# VARIABLE_DC_SUPPLY_schematic.net
KiCad netlist of a schematic drawn in EAGLE
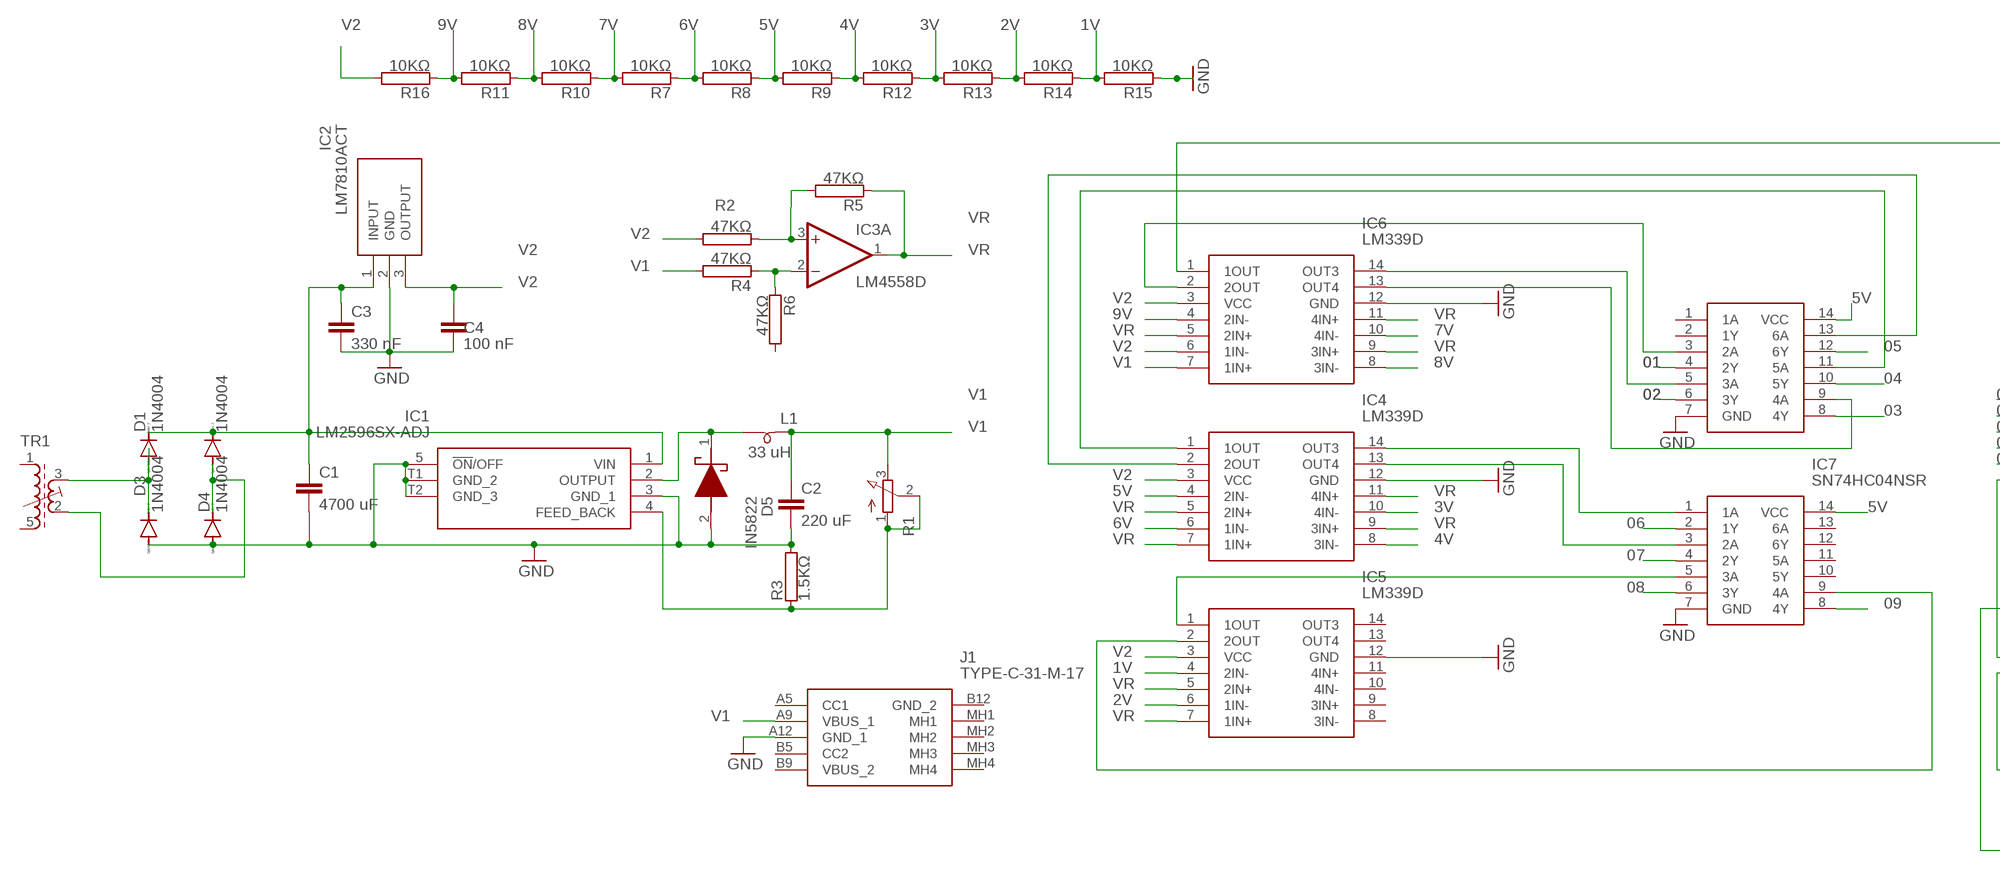
[diagram p0: schematic, sheet 1, part 1 of 2]
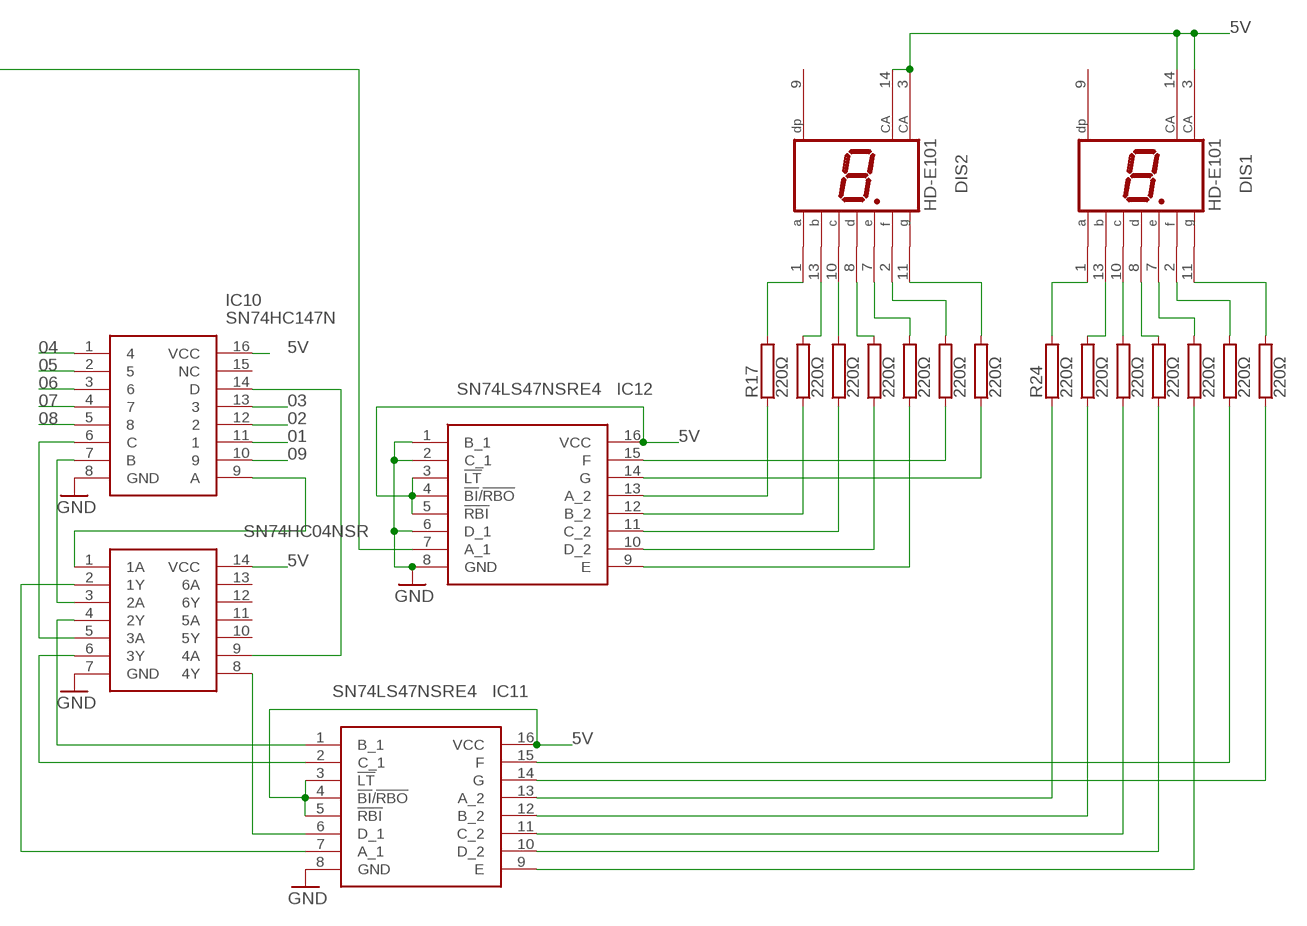
[diagram p1: schematic, sheet 1, part 2 of 2]

(export (version "E")
  (design (tool "Eeschema 10.0.6"))
  (components
    (comp (ref "C1")
      (value "4700 uF")
      (footprint "eagle-import:C2.5-2")
      (libsource (lib "eagle-import") (part "C2.5/2"))
    )
    (comp (ref "C2")
      (value "220 uF")
      (footprint "eagle-import:C2.5-2")
      (libsource (lib "eagle-import") (part "C2.5/2"))
    )
    (comp (ref "C3")
      (value "330 nF")
      (footprint "eagle-import:C2.5-2")
      (libsource (lib "eagle-import") (part "C2.5/2"))
    )
    (comp (ref "C4")
      (value "100 nF")
      (footprint "eagle-import:C2.5-2")
      (libsource (lib "eagle-import") (part "C2.5/2"))
    )
    (comp (ref "D1")
      (value "1N4004")
      (footprint "eagle-import:DO41-10")
      (libsource (lib "eagle-import") (part "1N4004"))
    )
    (comp (ref "D2")
      (value "1N4004")
      (footprint "eagle-import:DO41-10")
      (libsource (lib "eagle-import") (part "1N4004"))
    )
    (comp (ref "D3")
      (value "1N4004")
      (footprint "eagle-import:DO41-10")
      (libsource (lib "eagle-import") (part "1N4004"))
    )
    (comp (ref "D4")
      (value "1N4004")
      (footprint "eagle-import:DO41-10")
      (libsource (lib "eagle-import") (part "1N4004"))
    )
    (comp (ref "D5")
      (value "IN5822")
      (footprint "eagle-import:DIOAD3020W130L900D530")
      (libsource (lib "eagle-import") (part "IN5822"))
    )
    (comp (ref "DIS1")
      (value "HD-E101")
      (footprint "eagle-import:HDSP-I")
      (libsource (lib "eagle-import") (part "HD-E101"))
    )
    (comp (ref "DIS2")
      (value "HD-E101")
      (footprint "eagle-import:HDSP-I")
      (libsource (lib "eagle-import") (part "HD-E101"))
    )
    (comp (ref "IC1")
      (value "LM2596SX-ADJ")
      (footprint "eagle-import:LM2596SXADJ")
      (fields (field (name "MOUSER_PART_NUMBER") "926-LM2596SX-ADJ"))
      (libsource (lib "eagle-import") (part "LM2596SX-ADJ"))
    )
    (comp (ref "IC2")
      (value "LM7810ACT")
      (footprint "eagle-import:TO254P470X1016X2019-3P")
      (fields (field (name "MOUSER_PART_NUMBER") "512-LM7810ACT"))
      (libsource (lib "eagle-import") (part "LM7810ACT"))
    )
    (comp (ref "IC3")
      (value "LM4558D")
      (footprint "eagle-import:SO08")
      (libsource (lib "eagle-import") (part "4558DLM"))
    )
    (comp (ref "IC4")
      (value "LM339D")
      (footprint "eagle-import:SOIC127P600X175-14N")
      (fields (field (name "MOUSER_PART_NUMBER") "595-LM339D"))
      (libsource (lib "eagle-import") (part "LM339D"))
    )
    (comp (ref "IC5")
      (value "LM339D")
      (footprint "eagle-import:SOIC127P600X175-14N")
      (fields (field (name "MOUSER_PART_NUMBER") "595-LM339D"))
      (libsource (lib "eagle-import") (part "LM339D"))
    )
    (comp (ref "IC6")
      (value "LM339D")
      (footprint "eagle-import:SOIC127P600X175-14N")
      (fields (field (name "MOUSER_PART_NUMBER") "595-LM339D"))
      (libsource (lib "eagle-import") (part "LM339D"))
    )
    (comp (ref "IC7")
      (value "SN74HC04NSR")
      (footprint "eagle-import:SOIC127P780X200-14N")
      (fields (field (name "MOUSER_PART_NUMBER") "595-SN74HC04NSR"))
      (libsource (lib "eagle-import") (part "SN74HC04NSR"))
    )
    (comp (ref "IC8")
      (value "SN74HC04NSR")
      (footprint "eagle-import:SOIC127P780X200-14N")
      (fields (field (name "MOUSER_PART_NUMBER") "595-SN74HC04NSR"))
      (libsource (lib "eagle-import") (part "SN74HC04NSR"))
    )
    (comp (ref "IC9")
      (value "SN74HC04NSR")
      (footprint "eagle-import:SOIC127P780X200-14N")
      (fields (field (name "MOUSER_PART_NUMBER") "595-SN74HC04NSR"))
      (libsource (lib "eagle-import") (part "SN74HC04NSR"))
    )
    (comp (ref "IC10")
      (value "SN74HC147N")
      (footprint "eagle-import:DIP794W53P254L1930H508Q16N")
      (libsource (lib "eagle-import") (part "SN74HC147N"))
    )
    (comp (ref "IC11")
      (value "SN74LS47NSRE4")
      (footprint "eagle-import:SOIC127P780X200-16N")
      (libsource (lib "eagle-import") (part "SN74LS47NSRE4"))
    )
    (comp (ref "IC12")
      (value "SN74LS47NSRE4")
      (footprint "eagle-import:SOIC127P780X200-16N")
      (libsource (lib "eagle-import") (part "SN74LS47NSRE4"))
    )
    (comp (ref "J1")
      (value "TYPE-C-31-M-17")
      (footprint "eagle-import:TYPEC31M17")
      (libsource (lib "eagle-import") (part "TYPE-C-31-M-17"))
    )
    (comp (ref "L1")
      (value "33 uH")
      (footprint "eagle-import:SM-B5")
      (libsource (lib "eagle-import") (part "SM-B5"))
    )
    (comp (ref "R1")
      (value "3RP/1610N")
      (footprint "eagle-import:3RP_1610N")
      (libsource (lib "eagle-import") (part "3RP/1610N"))
    )
    (comp (ref "R2")
      (value "47KΩ")
      (footprint "eagle-import:TO-247-2V")
      (libsource (lib "eagle-import") (part "RMG100-V"))
    )
    (comp (ref "R3")
      (value "1.5KΩ")
      (footprint "eagle-import:TO-247-2V")
      (libsource (lib "eagle-import") (part "RMG100-V"))
    )
    (comp (ref "R4")
      (value "47KΩ")
      (footprint "eagle-import:TO-247-2V")
      (libsource (lib "eagle-import") (part "RMG100-V"))
    )
    (comp (ref "R5")
      (value "47KΩ")
      (footprint "eagle-import:TO-247-2V")
      (libsource (lib "eagle-import") (part "RMG100-V"))
    )
    (comp (ref "R6")
      (value "47KΩ")
      (footprint "eagle-import:TO-247-2V")
      (libsource (lib "eagle-import") (part "RMG100-V"))
    )
    (comp (ref "R7")
      (value "10KΩ")
      (footprint "eagle-import:TO-247-2V")
      (libsource (lib "eagle-import") (part "RMG100-V"))
    )
    (comp (ref "R8")
      (value "10KΩ")
      (footprint "eagle-import:TO-247-2V")
      (libsource (lib "eagle-import") (part "RMG100-V"))
    )
    (comp (ref "R9")
      (value "10KΩ")
      (footprint "eagle-import:TO-247-2V")
      (libsource (lib "eagle-import") (part "RMG100-V"))
    )
    (comp (ref "R10")
      (value "10KΩ")
      (footprint "eagle-import:TO-247-2V")
      (libsource (lib "eagle-import") (part "RMG100-V"))
    )
    (comp (ref "R11")
      (value "10KΩ")
      (footprint "eagle-import:TO-247-2V")
      (libsource (lib "eagle-import") (part "RMG100-V"))
    )
    (comp (ref "R12")
      (value "10KΩ")
      (footprint "eagle-import:TO-247-2V")
      (libsource (lib "eagle-import") (part "RMG100-V"))
    )
    (comp (ref "R13")
      (value "10KΩ")
      (footprint "eagle-import:TO-247-2V")
      (libsource (lib "eagle-import") (part "RMG100-V"))
    )
    (comp (ref "R14")
      (value "10KΩ")
      (footprint "eagle-import:TO-247-2V")
      (libsource (lib "eagle-import") (part "RMG100-V"))
    )
    (comp (ref "R15")
      (value "10KΩ")
      (footprint "eagle-import:TO-247-2V")
      (libsource (lib "eagle-import") (part "RMG100-V"))
    )
    (comp (ref "R16")
      (value "10KΩ")
      (footprint "eagle-import:TO-247-2V")
      (libsource (lib "eagle-import") (part "RMG100-V"))
    )
    (comp (ref "R17")
      (value "220Ω")
      (footprint "eagle-import:TO-247-2V")
      (libsource (lib "eagle-import") (part "RMG100-V"))
    )
    (comp (ref "R18")
      (value "220Ω")
      (footprint "eagle-import:TO-247-2V")
      (libsource (lib "eagle-import") (part "RMG100-V"))
    )
    (comp (ref "R19")
      (value "220Ω")
      (footprint "eagle-import:TO-247-2V")
      (libsource (lib "eagle-import") (part "RMG100-V"))
    )
    (comp (ref "R20")
      (value "220Ω")
      (footprint "eagle-import:TO-247-2V")
      (libsource (lib "eagle-import") (part "RMG100-V"))
    )
    (comp (ref "R21")
      (value "220Ω")
      (footprint "eagle-import:TO-247-2V")
      (libsource (lib "eagle-import") (part "RMG100-V"))
    )
    (comp (ref "R22")
      (value "220Ω")
      (footprint "eagle-import:TO-247-2V")
      (libsource (lib "eagle-import") (part "RMG100-V"))
    )
    (comp (ref "R23")
      (value "220Ω")
      (footprint "eagle-import:TO-247-2V")
      (libsource (lib "eagle-import") (part "RMG100-V"))
    )
    (comp (ref "R24")
      (value "220Ω")
      (footprint "eagle-import:TO-247-2V")
      (libsource (lib "eagle-import") (part "RMG100-V"))
    )
    (comp (ref "R25")
      (value "220Ω")
      (footprint "eagle-import:TO-247-2V")
      (libsource (lib "eagle-import") (part "RMG100-V"))
    )
    (comp (ref "R26")
      (value "220Ω")
      (footprint "eagle-import:TO-247-2V")
      (libsource (lib "eagle-import") (part "RMG100-V"))
    )
    (comp (ref "R27")
      (value "220Ω")
      (footprint "eagle-import:TO-247-2V")
      (libsource (lib "eagle-import") (part "RMG100-V"))
    )
    (comp (ref "R28")
      (value "220Ω")
      (footprint "eagle-import:TO-247-2V")
      (libsource (lib "eagle-import") (part "RMG100-V"))
    )
    (comp (ref "R29")
      (value "220Ω")
      (footprint "eagle-import:TO-247-2V")
      (libsource (lib "eagle-import") (part "RMG100-V"))
    )
    (comp (ref "R30")
      (value "220Ω")
      (footprint "eagle-import:TO-247-2V")
      (libsource (lib "eagle-import") (part "RMG100-V"))
    )
    (comp (ref "TR1")
      (value "71-4-1532")
      (footprint "eagle-import:71-5")
      (libsource (lib "eagle-import") (part "71-4-1532"))
    )
  )
  (nets
    (net (code "1") (name "/01") (class "Default")
      (node (ref "IC10") (pin "11") (pinfunction "1_11") (pintype "bidirectional"))
      (node (ref "IC8") (pin "4") (pinfunction "2Y_4") (pintype "bidirectional"))
    )
    (net (code "2") (name "/1V") (class "Default")
      (node (ref "IC5") (pin "4") (pinfunction "2IN-_4") (pintype "bidirectional"))
      (node (ref "R14") (pin "1") (pinfunction "1_1") (pintype "passive"))
      (node (ref "R15") (pin "2") (pinfunction "2_2") (pintype "passive"))
    )
    (net (code "3") (name "/02") (class "Default")
      (node (ref "IC10") (pin "12") (pinfunction "2_12") (pintype "bidirectional"))
      (node (ref "IC8") (pin "6") (pinfunction "3Y_6") (pintype "bidirectional"))
    )
    (net (code "4") (name "/2V") (class "Default")
      (node (ref "IC5") (pin "6") (pinfunction "1IN-_6") (pintype "bidirectional"))
      (node (ref "R13") (pin "1") (pinfunction "1_1") (pintype "passive"))
      (node (ref "R14") (pin "2") (pinfunction "2_2") (pintype "passive"))
    )
    (net (code "5") (name "/03") (class "Default")
      (node (ref "IC10") (pin "13") (pinfunction "3_13") (pintype "bidirectional"))
      (node (ref "IC8") (pin "8") (pinfunction "4Y_8") (pintype "bidirectional"))
    )
    (net (code "6") (name "/3V") (class "Default")
      (node (ref "IC4") (pin "10") (pinfunction "4IN-_10") (pintype "bidirectional"))
      (node (ref "R12") (pin "1") (pinfunction "1_1") (pintype "passive"))
      (node (ref "R13") (pin "2") (pinfunction "2_2") (pintype "passive"))
    )
    (net (code "7") (name "/04") (class "Default")
      (node (ref "IC10") (pin "1") (pinfunction "4_1") (pintype "bidirectional"))
      (node (ref "IC8") (pin "10") (pinfunction "5Y_10") (pintype "bidirectional"))
    )
    (net (code "8") (name "/4V") (class "Default")
      (node (ref "IC4") (pin "8") (pinfunction "3IN-_8") (pintype "bidirectional"))
      (node (ref "R12") (pin "2") (pinfunction "2_2") (pintype "passive"))
      (node (ref "R9") (pin "1") (pinfunction "1_1") (pintype "passive"))
    )
    (net (code "9") (name "/05") (class "Default")
      (node (ref "IC10") (pin "2") (pinfunction "5_2") (pintype "bidirectional"))
      (node (ref "IC8") (pin "12") (pinfunction "6Y_12") (pintype "bidirectional"))
    )
    (net (code "10") (name "/5V") (class "Default")
      (node (ref "DIS1") (pin "14") (pinfunction "CA_14") (pintype "passive"))
      (node (ref "DIS1") (pin "3") (pinfunction "CA_3") (pintype "passive"))
      (node (ref "DIS2") (pin "14") (pinfunction "CA_14") (pintype "passive"))
      (node (ref "DIS2") (pin "3") (pinfunction "CA_3") (pintype "passive"))
      (node (ref "IC10") (pin "16") (pinfunction "VCC_16") (pintype "bidirectional"))
      (node (ref "IC11") (pin "16") (pinfunction "VCC_16") (pintype "bidirectional"))
      (node (ref "IC11") (pin "3") (pinfunction "~{LT}_3") (pintype "bidirectional"))
      (node (ref "IC11") (pin "4") (pinfunction "~{BI}/~{RBO}_4") (pintype "bidirectional"))
      (node (ref "IC11") (pin "5") (pinfunction "~{RBI}_5") (pintype "bidirectional"))
      (node (ref "IC12") (pin "16") (pinfunction "VCC_16") (pintype "bidirectional"))
      (node (ref "IC12") (pin "3") (pinfunction "~{LT}_3") (pintype "bidirectional"))
      (node (ref "IC12") (pin "4") (pinfunction "~{BI}/~{RBO}_4") (pintype "bidirectional"))
      (node (ref "IC12") (pin "5") (pinfunction "~{RBI}_5") (pintype "bidirectional"))
      (node (ref "IC4") (pin "4") (pinfunction "2IN-_4") (pintype "bidirectional"))
      (node (ref "IC7") (pin "14") (pinfunction "VCC_14") (pintype "bidirectional"))
      (node (ref "IC8") (pin "14") (pinfunction "VCC_14") (pintype "bidirectional"))
      (node (ref "IC9") (pin "14") (pinfunction "VCC_14") (pintype "bidirectional"))
      (node (ref "R8") (pin "1") (pinfunction "1_1") (pintype "passive"))
      (node (ref "R9") (pin "2") (pinfunction "2_2") (pintype "passive"))
    )
    (net (code "11") (name "/06") (class "Default")
      (node (ref "IC10") (pin "3") (pinfunction "6_3") (pintype "bidirectional"))
      (node (ref "IC7") (pin "2") (pinfunction "1Y_2") (pintype "bidirectional"))
    )
    (net (code "12") (name "/6V") (class "Default")
      (node (ref "IC4") (pin "6") (pinfunction "1IN-_6") (pintype "bidirectional"))
      (node (ref "R7") (pin "1") (pinfunction "1_1") (pintype "passive"))
      (node (ref "R8") (pin "2") (pinfunction "2_2") (pintype "passive"))
    )
    (net (code "13") (name "/07") (class "Default")
      (node (ref "IC10") (pin "4") (pinfunction "7_4") (pintype "bidirectional"))
      (node (ref "IC7") (pin "4") (pinfunction "2Y_4") (pintype "bidirectional"))
    )
    (net (code "14") (name "/7V") (class "Default")
      (node (ref "IC6") (pin "10") (pinfunction "4IN-_10") (pintype "bidirectional"))
      (node (ref "R10") (pin "1") (pinfunction "1_1") (pintype "passive"))
      (node (ref "R7") (pin "2") (pinfunction "2_2") (pintype "passive"))
    )
    (net (code "15") (name "/08") (class "Default")
      (node (ref "IC10") (pin "5") (pinfunction "8_5") (pintype "bidirectional"))
      (node (ref "IC7") (pin "6") (pinfunction "3Y_6") (pintype "bidirectional"))
    )
    (net (code "16") (name "/8V") (class "Default")
      (node (ref "IC6") (pin "8") (pinfunction "3IN-_8") (pintype "bidirectional"))
      (node (ref "R10") (pin "2") (pinfunction "2_2") (pintype "passive"))
      (node (ref "R11") (pin "1") (pinfunction "1_1") (pintype "passive"))
    )
    (net (code "17") (name "/09") (class "Default")
      (node (ref "IC10") (pin "10") (pinfunction "9_10") (pintype "bidirectional"))
      (node (ref "IC7") (pin "8") (pinfunction "4Y_8") (pintype "bidirectional"))
    )
    (net (code "18") (name "/9V") (class "Default")
      (node (ref "IC6") (pin "4") (pinfunction "2IN-_4") (pintype "bidirectional"))
      (node (ref "R11") (pin "2") (pinfunction "2_2") (pintype "passive"))
      (node (ref "R16") (pin "1") (pinfunction "1_1") (pintype "passive"))
    )
    (net (code "19") (name "/V1") (class "Default")
      (node (ref "C2") (pin "1") (pinfunction "1_1") (pintype "passive"))
      (node (ref "IC6") (pin "7") (pinfunction "1IN+_7") (pintype "bidirectional"))
      (node (ref "J1") (pin "A9") (pinfunction "VBUS_1_A9") (pintype "bidirectional"))
      (node (ref "L1") (pin "2") (pinfunction "2_2") (pintype "passive"))
      (node (ref "R1") (pin "3") (pinfunction "E_3") (pintype "passive"))
      (node (ref "R4") (pin "2") (pinfunction "2_2") (pintype "passive"))
    )
    (net (code "20") (name "/V2") (class "Default")
      (node (ref "C4") (pin "1") (pinfunction "1_1") (pintype "passive"))
      (node (ref "IC2") (pin "3") (pinfunction "OUTPUT_3") (pintype "bidirectional"))
      (node (ref "IC4") (pin "3") (pinfunction "VCC_3") (pintype "bidirectional"))
      (node (ref "IC5") (pin "3") (pinfunction "VCC_3") (pintype "bidirectional"))
      (node (ref "IC6") (pin "3") (pinfunction "VCC_3") (pintype "bidirectional"))
      (node (ref "IC6") (pin "6") (pinfunction "1IN-_6") (pintype "bidirectional"))
      (node (ref "R16") (pin "2") (pinfunction "2_2") (pintype "passive"))
      (node (ref "R2") (pin "2") (pinfunction "2_2") (pintype "passive"))
    )
    (net (code "21") (name "/VR") (class "Default")
      (node (ref "IC3") (pin "1") (pinfunction "OUT_1") (pintype "output"))
      (node (ref "IC4") (pin "11") (pinfunction "4IN+_11") (pintype "bidirectional"))
      (node (ref "IC4") (pin "5") (pinfunction "2IN+_5") (pintype "bidirectional"))
      (node (ref "IC4") (pin "7") (pinfunction "1IN+_7") (pintype "bidirectional"))
      (node (ref "IC4") (pin "9") (pinfunction "3IN+_9") (pintype "bidirectional"))
      (node (ref "IC5") (pin "5") (pinfunction "2IN+_5") (pintype "bidirectional"))
      (node (ref "IC5") (pin "7") (pinfunction "1IN+_7") (pintype "bidirectional"))
      (node (ref "IC6") (pin "11") (pinfunction "4IN+_11") (pintype "bidirectional"))
      (node (ref "IC6") (pin "5") (pinfunction "2IN+_5") (pintype "bidirectional"))
      (node (ref "IC6") (pin "9") (pinfunction "3IN+_9") (pintype "bidirectional"))
      (node (ref "R5") (pin "1") (pinfunction "1_1") (pintype "passive"))
    )
    (net (code "22") (name "GND") (class "Default")
      (node (ref "C1") (pin "2") (pinfunction "2_2") (pintype "passive"))
      (node (ref "C2") (pin "2") (pinfunction "2_2") (pintype "passive"))
      (node (ref "C3") (pin "2") (pinfunction "2_2") (pintype "passive"))
      (node (ref "C4") (pin "2") (pinfunction "2_2") (pintype "passive"))
      (node (ref "D3") (pin "A") (pinfunction "A_A") (pintype "passive"))
      (node (ref "D4") (pin "A") (pinfunction "A_A") (pintype "passive"))
      (node (ref "D5") (pin "2") (pinfunction "A_2") (pintype "bidirectional"))
      (node (ref "IC1") (pin "3") (pinfunction "GND_1_3") (pintype "bidirectional"))
      (node (ref "IC1") (pin "5") (pinfunction "~{ON}/OFF_5") (pintype "bidirectional"))
      (node (ref "IC1") (pin "T1") (pinfunction "GND_2_T1") (pintype "bidirectional"))
      (node (ref "IC1") (pin "T2") (pinfunction "GND_3_T2") (pintype "bidirectional"))
      (node (ref "IC10") (pin "8") (pinfunction "GND_8") (pintype "bidirectional"))
      (node (ref "IC11") (pin "8") (pinfunction "GND_8") (pintype "bidirectional"))
      (node (ref "IC12") (pin "1") (pinfunction "B_1_1") (pintype "bidirectional"))
      (node (ref "IC12") (pin "2") (pinfunction "C_1_2") (pintype "bidirectional"))
      (node (ref "IC12") (pin "6") (pinfunction "D_1_6") (pintype "bidirectional"))
      (node (ref "IC12") (pin "8") (pinfunction "GND_8") (pintype "bidirectional"))
      (node (ref "IC2") (pin "2") (pinfunction "GND_2") (pintype "bidirectional"))
      (node (ref "IC4") (pin "12") (pinfunction "GND_12") (pintype "bidirectional"))
      (node (ref "IC5") (pin "12") (pinfunction "GND_12") (pintype "bidirectional"))
      (node (ref "IC6") (pin "12") (pinfunction "GND_12") (pintype "bidirectional"))
      (node (ref "IC7") (pin "7") (pinfunction "GND_7") (pintype "bidirectional"))
      (node (ref "IC8") (pin "7") (pinfunction "GND_7") (pintype "bidirectional"))
      (node (ref "IC9") (pin "7") (pinfunction "GND_7") (pintype "bidirectional"))
      (node (ref "J1") (pin "A12") (pinfunction "GND_1_A12") (pintype "bidirectional"))
      (node (ref "R15") (pin "1") (pinfunction "1_1") (pintype "passive"))
      (node (ref "R3") (pin "2") (pinfunction "2_2") (pintype "passive"))
    )
    (net (code "23") (name "Net-(D5-K)") (class "Default")
      (node (ref "D5") (pin "1") (pinfunction "K_1") (pintype "bidirectional"))
      (node (ref "IC1") (pin "2") (pinfunction "OUTPUT_2") (pintype "bidirectional"))
      (node (ref "L1") (pin "1") (pinfunction "1_1") (pintype "passive"))
    )
    (net (code "24") (name "Net-(DIS1-A)") (class "Default")
      (node (ref "DIS1") (pin "1") (pinfunction "A_1") (pintype "passive"))
      (node (ref "R24") (pin "2") (pinfunction "2_2") (pintype "passive"))
    )
    (net (code "25") (name "Net-(DIS1-B)") (class "Default")
      (node (ref "DIS1") (pin "13") (pinfunction "B_13") (pintype "passive"))
      (node (ref "R25") (pin "2") (pinfunction "2_2") (pintype "passive"))
    )
    (net (code "26") (name "Net-(DIS1-C)") (class "Default")
      (node (ref "DIS1") (pin "10") (pinfunction "C_10") (pintype "passive"))
      (node (ref "R26") (pin "2") (pinfunction "2_2") (pintype "passive"))
    )
    (net (code "27") (name "Net-(DIS1-D)") (class "Default")
      (node (ref "DIS1") (pin "8") (pinfunction "D_8") (pintype "passive"))
      (node (ref "R27") (pin "2") (pinfunction "2_2") (pintype "passive"))
    )
    (net (code "28") (name "Net-(DIS1-E)") (class "Default")
      (node (ref "DIS1") (pin "7") (pinfunction "E_7") (pintype "passive"))
      (node (ref "R28") (pin "2") (pinfunction "2_2") (pintype "passive"))
    )
    (net (code "29") (name "Net-(DIS1-F)") (class "Default")
      (node (ref "DIS1") (pin "2") (pinfunction "F_2") (pintype "passive"))
      (node (ref "R29") (pin "2") (pinfunction "2_2") (pintype "passive"))
    )
    (net (code "30") (name "Net-(DIS1-G)") (class "Default")
      (node (ref "DIS1") (pin "11") (pinfunction "G_11") (pintype "passive"))
      (node (ref "R30") (pin "2") (pinfunction "2_2") (pintype "passive"))
    )
    (net (code "31") (name "Net-(DIS2-A)") (class "Default")
      (node (ref "DIS2") (pin "1") (pinfunction "A_1") (pintype "passive"))
      (node (ref "R17") (pin "2") (pinfunction "2_2") (pintype "passive"))
    )
    (net (code "32") (name "Net-(DIS2-B)") (class "Default")
      (node (ref "DIS2") (pin "13") (pinfunction "B_13") (pintype "passive"))
      (node (ref "R18") (pin "2") (pinfunction "2_2") (pintype "passive"))
    )
    (net (code "33") (name "Net-(DIS2-C)") (class "Default")
      (node (ref "DIS2") (pin "10") (pinfunction "C_10") (pintype "passive"))
      (node (ref "R19") (pin "2") (pinfunction "2_2") (pintype "passive"))
    )
    (net (code "34") (name "Net-(DIS2-D)") (class "Default")
      (node (ref "DIS2") (pin "8") (pinfunction "D_8") (pintype "passive"))
      (node (ref "R20") (pin "2") (pinfunction "2_2") (pintype "passive"))
    )
    (net (code "35") (name "Net-(DIS2-E)") (class "Default")
      (node (ref "DIS2") (pin "7") (pinfunction "E_7") (pintype "passive"))
      (node (ref "R21") (pin "2") (pinfunction "2_2") (pintype "passive"))
    )
    (net (code "36") (name "Net-(DIS2-F)") (class "Default")
      (node (ref "DIS2") (pin "2") (pinfunction "F_2") (pintype "passive"))
      (node (ref "R22") (pin "2") (pinfunction "2_2") (pintype "passive"))
    )
    (net (code "37") (name "Net-(DIS2-G)") (class "Default")
      (node (ref "DIS2") (pin "11") (pinfunction "G_11") (pintype "passive"))
      (node (ref "R23") (pin "2") (pinfunction "2_2") (pintype "passive"))
    )
    (net (code "38") (name "Net-(IC1-FEED_BACK)") (class "Default")
      (node (ref "IC1") (pin "4") (pinfunction "FEED_BACK_4") (pintype "bidirectional"))
      (node (ref "R1") (pin "1") (pinfunction "A_1") (pintype "passive"))
      (node (ref "R1") (pin "2") (pinfunction "S_2") (pintype "passive"))
      (node (ref "R3") (pin "1") (pinfunction "1_1") (pintype "passive"))
    )
    (net (code "39") (name "Net-(IC1-VIN)") (class "Default")
      (node (ref "C1") (pin "1") (pinfunction "1_1") (pintype "passive"))
      (node (ref "C3") (pin "1") (pinfunction "1_1") (pintype "passive"))
      (node (ref "D1") (pin "C") (pinfunction "C_C") (pintype "passive"))
      (node (ref "D2") (pin "C") (pinfunction "C_C") (pintype "passive"))
      (node (ref "IC1") (pin "1") (pinfunction "VIN_1") (pintype "bidirectional"))
      (node (ref "IC2") (pin "1") (pinfunction "INPUT_1") (pintype "bidirectional"))
    )
    (net (code "40") (name "Net-(IC3A-+IN)") (class "Default")
      (node (ref "IC3") (pin "3") (pinfunction "+IN_3") (pintype "input"))
      (node (ref "R2") (pin "1") (pinfunction "1_1") (pintype "passive"))
      (node (ref "R5") (pin "2") (pinfunction "2_2") (pintype "passive"))
    )
    (net (code "41") (name "Net-(IC3A--IN)") (class "Default")
      (node (ref "IC3") (pin "2") (pinfunction "-IN_2") (pintype "input"))
      (node (ref "R4") (pin "1") (pinfunction "1_1") (pintype "passive"))
      (node (ref "R6") (pin "1") (pinfunction "1_1") (pintype "passive"))
    )
    (net (code "42") (name "Net-(IC4-1OUT)") (class "Default")
      (node (ref "IC4") (pin "1") (pinfunction "1OUT_1") (pintype "bidirectional"))
      (node (ref "IC8") (pin "11") (pinfunction "5A_11") (pintype "bidirectional"))
    )
    (net (code "43") (name "Net-(IC4-2OUT)") (class "Default")
      (node (ref "IC4") (pin "2") (pinfunction "2OUT_2") (pintype "bidirectional"))
      (node (ref "IC8") (pin "13") (pinfunction "6A_13") (pintype "bidirectional"))
    )
    (net (code "44") (name "Net-(IC4-OUT3)") (class "Default")
      (node (ref "IC4") (pin "14") (pinfunction "OUT3_14") (pintype "bidirectional"))
      (node (ref "IC7") (pin "1") (pinfunction "1A_1") (pintype "bidirectional"))
    )
    (net (code "45") (name "Net-(IC4-OUT4)") (class "Default")
      (node (ref "IC4") (pin "13") (pinfunction "OUT4_13") (pintype "bidirectional"))
      (node (ref "IC7") (pin "3") (pinfunction "2A_3") (pintype "bidirectional"))
    )
    (net (code "46") (name "Net-(IC5-1OUT)") (class "Default")
      (node (ref "IC5") (pin "1") (pinfunction "1OUT_1") (pintype "bidirectional"))
      (node (ref "IC7") (pin "5") (pinfunction "3A_5") (pintype "bidirectional"))
    )
    (net (code "47") (name "Net-(IC5-2OUT)") (class "Default")
      (node (ref "IC5") (pin "2") (pinfunction "2OUT_2") (pintype "bidirectional"))
      (node (ref "IC7") (pin "9") (pinfunction "4A_9") (pintype "bidirectional"))
    )
    (net (code "48") (name "Net-(IC6-2OUT)") (class "Default")
      (node (ref "IC6") (pin "2") (pinfunction "2OUT_2") (pintype "bidirectional"))
      (node (ref "IC8") (pin "3") (pinfunction "2A_3") (pintype "bidirectional"))
    )
    (net (code "49") (name "Net-(IC6-OUT3)") (class "Default")
      (node (ref "IC6") (pin "14") (pinfunction "OUT3_14") (pintype "bidirectional"))
      (node (ref "IC8") (pin "5") (pinfunction "3A_5") (pintype "bidirectional"))
    )
    (net (code "50") (name "Net-(IC6-OUT4)") (class "Default")
      (node (ref "IC6") (pin "13") (pinfunction "OUT4_13") (pintype "bidirectional"))
      (node (ref "IC8") (pin "9") (pinfunction "4A_9") (pintype "bidirectional"))
    )
    (net (code "51") (name "Net-(IC10-A)") (class "Default")
      (node (ref "IC10") (pin "9") (pinfunction "A_9") (pintype "bidirectional"))
      (node (ref "IC9") (pin "1") (pinfunction "1A_1") (pintype "bidirectional"))
    )
    (net (code "52") (name "Net-(IC10-B)") (class "Default")
      (node (ref "IC10") (pin "7") (pinfunction "B_7") (pintype "bidirectional"))
      (node (ref "IC9") (pin "3") (pinfunction "2A_3") (pintype "bidirectional"))
    )
    (net (code "53") (name "Net-(IC10-C)") (class "Default")
      (node (ref "IC10") (pin "6") (pinfunction "C_6") (pintype "bidirectional"))
      (node (ref "IC9") (pin "5") (pinfunction "3A_5") (pintype "bidirectional"))
    )
    (net (code "54") (name "Net-(IC10-D)") (class "Default")
      (node (ref "IC10") (pin "14") (pinfunction "D_14") (pintype "bidirectional"))
      (node (ref "IC9") (pin "9") (pinfunction "4A_9") (pintype "bidirectional"))
    )
    (net (code "55") (name "Net-(IC11-A_1)") (class "Default")
      (node (ref "IC11") (pin "7") (pinfunction "A_1_7") (pintype "bidirectional"))
      (node (ref "IC9") (pin "2") (pinfunction "1Y_2") (pintype "bidirectional"))
    )
    (net (code "56") (name "Net-(IC11-A_2)") (class "Default")
      (node (ref "IC11") (pin "13") (pinfunction "A_2_13") (pintype "bidirectional"))
      (node (ref "R24") (pin "1") (pinfunction "1_1") (pintype "passive"))
    )
    (net (code "57") (name "Net-(IC11-B_1)") (class "Default")
      (node (ref "IC11") (pin "1") (pinfunction "B_1_1") (pintype "bidirectional"))
      (node (ref "IC9") (pin "4") (pinfunction "2Y_4") (pintype "bidirectional"))
    )
    (net (code "58") (name "Net-(IC11-B_2)") (class "Default")
      (node (ref "IC11") (pin "12") (pinfunction "B_2_12") (pintype "bidirectional"))
      (node (ref "R25") (pin "1") (pinfunction "1_1") (pintype "passive"))
    )
    (net (code "59") (name "Net-(IC11-C_1)") (class "Default")
      (node (ref "IC11") (pin "2") (pinfunction "C_1_2") (pintype "bidirectional"))
      (node (ref "IC9") (pin "6") (pinfunction "3Y_6") (pintype "bidirectional"))
    )
    (net (code "60") (name "Net-(IC11-C_2)") (class "Default")
      (node (ref "IC11") (pin "11") (pinfunction "C_2_11") (pintype "bidirectional"))
      (node (ref "R26") (pin "1") (pinfunction "1_1") (pintype "passive"))
    )
    (net (code "61") (name "Net-(IC11-D_1)") (class "Default")
      (node (ref "IC11") (pin "6") (pinfunction "D_1_6") (pintype "bidirectional"))
      (node (ref "IC9") (pin "8") (pinfunction "4Y_8") (pintype "bidirectional"))
    )
    (net (code "62") (name "Net-(IC11-D_2)") (class "Default")
      (node (ref "IC11") (pin "10") (pinfunction "D_2_10") (pintype "bidirectional"))
      (node (ref "R27") (pin "1") (pinfunction "1_1") (pintype "passive"))
    )
    (net (code "63") (name "Net-(IC11-E)") (class "Default")
      (node (ref "IC11") (pin "9") (pinfunction "E_9") (pintype "bidirectional"))
      (node (ref "R28") (pin "1") (pinfunction "1_1") (pintype "passive"))
    )
    (net (code "64") (name "Net-(IC11-F)") (class "Default")
      (node (ref "IC11") (pin "15") (pinfunction "F_15") (pintype "bidirectional"))
      (node (ref "R29") (pin "1") (pinfunction "1_1") (pintype "passive"))
    )
    (net (code "65") (name "Net-(IC11-G)") (class "Default")
      (node (ref "IC11") (pin "14") (pinfunction "G_14") (pintype "bidirectional"))
      (node (ref "R30") (pin "1") (pinfunction "1_1") (pintype "passive"))
    )
    (net (code "66") (name "Net-(IC12-A_1)") (class "Default")
      (node (ref "IC12") (pin "7") (pinfunction "A_1_7") (pintype "bidirectional"))
      (node (ref "IC6") (pin "1") (pinfunction "1OUT_1") (pintype "bidirectional"))
    )
    (net (code "67") (name "Net-(IC12-A_2)") (class "Default")
      (node (ref "IC12") (pin "13") (pinfunction "A_2_13") (pintype "bidirectional"))
      (node (ref "R17") (pin "1") (pinfunction "1_1") (pintype "passive"))
    )
    (net (code "68") (name "Net-(IC12-B_2)") (class "Default")
      (node (ref "IC12") (pin "12") (pinfunction "B_2_12") (pintype "bidirectional"))
      (node (ref "R18") (pin "1") (pinfunction "1_1") (pintype "passive"))
    )
    (net (code "69") (name "Net-(IC12-C_2)") (class "Default")
      (node (ref "IC12") (pin "11") (pinfunction "C_2_11") (pintype "bidirectional"))
      (node (ref "R19") (pin "1") (pinfunction "1_1") (pintype "passive"))
    )
    (net (code "70") (name "Net-(IC12-D_2)") (class "Default")
      (node (ref "IC12") (pin "10") (pinfunction "D_2_10") (pintype "bidirectional"))
      (node (ref "R20") (pin "1") (pinfunction "1_1") (pintype "passive"))
    )
    (net (code "71") (name "Net-(IC12-E)") (class "Default")
      (node (ref "IC12") (pin "9") (pinfunction "E_9") (pintype "bidirectional"))
      (node (ref "R21") (pin "1") (pinfunction "1_1") (pintype "passive"))
    )
    (net (code "72") (name "Net-(IC12-F)") (class "Default")
      (node (ref "IC12") (pin "15") (pinfunction "F_15") (pintype "bidirectional"))
      (node (ref "R22") (pin "1") (pinfunction "1_1") (pintype "passive"))
    )
    (net (code "73") (name "Net-(IC12-G)") (class "Default")
      (node (ref "IC12") (pin "14") (pinfunction "G_14") (pintype "bidirectional"))
      (node (ref "R23") (pin "1") (pinfunction "1_1") (pintype "passive"))
    )
    (net (code "74") (name "Net-(TR1A-A2)") (class "Default")
      (node (ref "D1") (pin "A") (pinfunction "A_A") (pintype "passive"))
      (node (ref "D3") (pin "C") (pinfunction "C_C") (pintype "passive"))
      (node (ref "TR1") (pin "3") (pinfunction "A2_3") (pintype "passive"))
    )
    (net (code "75") (name "Net-(TR1A-E2)") (class "Default")
      (node (ref "D2") (pin "A") (pinfunction "A_A") (pintype "passive"))
      (node (ref "D4") (pin "C") (pinfunction "C_C") (pintype "passive"))
      (node (ref "TR1") (pin "2") (pinfunction "E2_2") (pintype "passive"))
    )
    (net (code "76") (name "unconnected-(DIS1-DP-Pad9)") (class "Default")
      (node (ref "DIS1") (pin "9") (pinfunction "DP_9") (pintype "passive"))
    )
    (net (code "77") (name "unconnected-(DIS2-DP-Pad9)") (class "Default")
      (node (ref "DIS2") (pin "9") (pinfunction "DP_9") (pintype "passive"))
    )
    (net (code "78") (name "unconnected-(IC5-3IN+-Pad9)") (class "Default")
      (node (ref "IC5") (pin "9") (pinfunction "3IN+_9") (pintype "bidirectional"))
    )
    (net (code "79") (name "unconnected-(IC5-3IN--Pad8)") (class "Default")
      (node (ref "IC5") (pin "8") (pinfunction "3IN-_8") (pintype "bidirectional"))
    )
    (net (code "80") (name "unconnected-(IC5-4IN+-Pad11)") (class "Default")
      (node (ref "IC5") (pin "11") (pinfunction "4IN+_11") (pintype "bidirectional"))
    )
    (net (code "81") (name "unconnected-(IC5-4IN--Pad10)") (class "Default")
      (node (ref "IC5") (pin "10") (pinfunction "4IN-_10") (pintype "bidirectional"))
    )
    (net (code "82") (name "unconnected-(IC5-OUT3-Pad14)") (class "Default")
      (node (ref "IC5") (pin "14") (pinfunction "OUT3_14") (pintype "bidirectional"))
    )
    (net (code "83") (name "unconnected-(IC5-OUT4-Pad13)") (class "Default")
      (node (ref "IC5") (pin "13") (pinfunction "OUT4_13") (pintype "bidirectional"))
    )
    (net (code "84") (name "unconnected-(IC7-5A-Pad11)") (class "Default")
      (node (ref "IC7") (pin "11") (pinfunction "5A_11") (pintype "bidirectional"))
    )
    (net (code "85") (name "unconnected-(IC7-5Y-Pad10)") (class "Default")
      (node (ref "IC7") (pin "10") (pinfunction "5Y_10") (pintype "bidirectional"))
    )
    (net (code "86") (name "unconnected-(IC7-6A-Pad13)") (class "Default")
      (node (ref "IC7") (pin "13") (pinfunction "6A_13") (pintype "bidirectional"))
    )
    (net (code "87") (name "unconnected-(IC7-6Y-Pad12)") (class "Default")
      (node (ref "IC7") (pin "12") (pinfunction "6Y_12") (pintype "bidirectional"))
    )
    (net (code "88") (name "unconnected-(IC8-1A-Pad1)") (class "Default")
      (node (ref "IC8") (pin "1") (pinfunction "1A_1") (pintype "bidirectional"))
    )
    (net (code "89") (name "unconnected-(IC8-1Y-Pad2)") (class "Default")
      (node (ref "IC8") (pin "2") (pinfunction "1Y_2") (pintype "bidirectional"))
    )
    (net (code "90") (name "unconnected-(IC9-5A-Pad11)") (class "Default")
      (node (ref "IC9") (pin "11") (pinfunction "5A_11") (pintype "bidirectional"))
    )
    (net (code "91") (name "unconnected-(IC9-5Y-Pad10)") (class "Default")
      (node (ref "IC9") (pin "10") (pinfunction "5Y_10") (pintype "bidirectional"))
    )
    (net (code "92") (name "unconnected-(IC9-6A-Pad13)") (class "Default")
      (node (ref "IC9") (pin "13") (pinfunction "6A_13") (pintype "bidirectional"))
    )
    (net (code "93") (name "unconnected-(IC9-6Y-Pad12)") (class "Default")
      (node (ref "IC9") (pin "12") (pinfunction "6Y_12") (pintype "bidirectional"))
    )
    (net (code "94") (name "unconnected-(IC10-NC-Pad15)") (class "Default")
      (node (ref "IC10") (pin "15") (pinfunction "NC_15") (pintype "no_connect"))
    )
    (net (code "95") (name "unconnected-(J1-CC1-PadA5)") (class "Default")
      (node (ref "J1") (pin "A5") (pinfunction "CC1_A5") (pintype "bidirectional"))
    )
    (net (code "96") (name "unconnected-(J1-CC2-PadB5)") (class "Default")
      (node (ref "J1") (pin "B5") (pinfunction "CC2_B5") (pintype "bidirectional"))
    )
    (net (code "97") (name "unconnected-(J1-GND_2-PadB12)") (class "Default")
      (node (ref "J1") (pin "B12") (pinfunction "GND_2_B12") (pintype "bidirectional"))
    )
    (net (code "98") (name "unconnected-(J1-PadMH1)") (class "Default")
      (node (ref "J1") (pin "MH1") (pinfunction "MH1_MH1") (pintype "bidirectional"))
    )
    (net (code "99") (name "unconnected-(J1-PadMH2)") (class "Default")
      (node (ref "J1") (pin "MH2") (pinfunction "MH2_MH2") (pintype "bidirectional"))
    )
    (net (code "100") (name "unconnected-(J1-PadMH3)") (class "Default")
      (node (ref "J1") (pin "MH3") (pinfunction "MH3_MH3") (pintype "bidirectional"))
    )
    (net (code "101") (name "unconnected-(J1-PadMH4)") (class "Default")
      (node (ref "J1") (pin "MH4") (pinfunction "MH4_MH4") (pintype "bidirectional"))
    )
    (net (code "102") (name "unconnected-(J1-VBUS_2-PadB9)") (class "Default")
      (node (ref "J1") (pin "B9") (pinfunction "VBUS_2_B9") (pintype "bidirectional"))
    )
    (net (code "103") (name "unconnected-(R6-Pad2)") (class "Default")
      (node (ref "R6") (pin "2") (pinfunction "2_2") (pintype "passive"))
    )
    (net (code "104") (name "unconnected-(TR1A-A1-Pad1)") (class "Default")
      (node (ref "TR1") (pin "1") (pinfunction "A1_1") (pintype "passive"))
    )
    (net (code "105") (name "unconnected-(TR1A-E1-Pad5)") (class "Default")
      (node (ref "TR1") (pin "5") (pinfunction "E1_5") (pintype "passive"))
    )
  )
)
